# Sheet1.net
KiCad netlist of a schematic drawn in Altium Designer
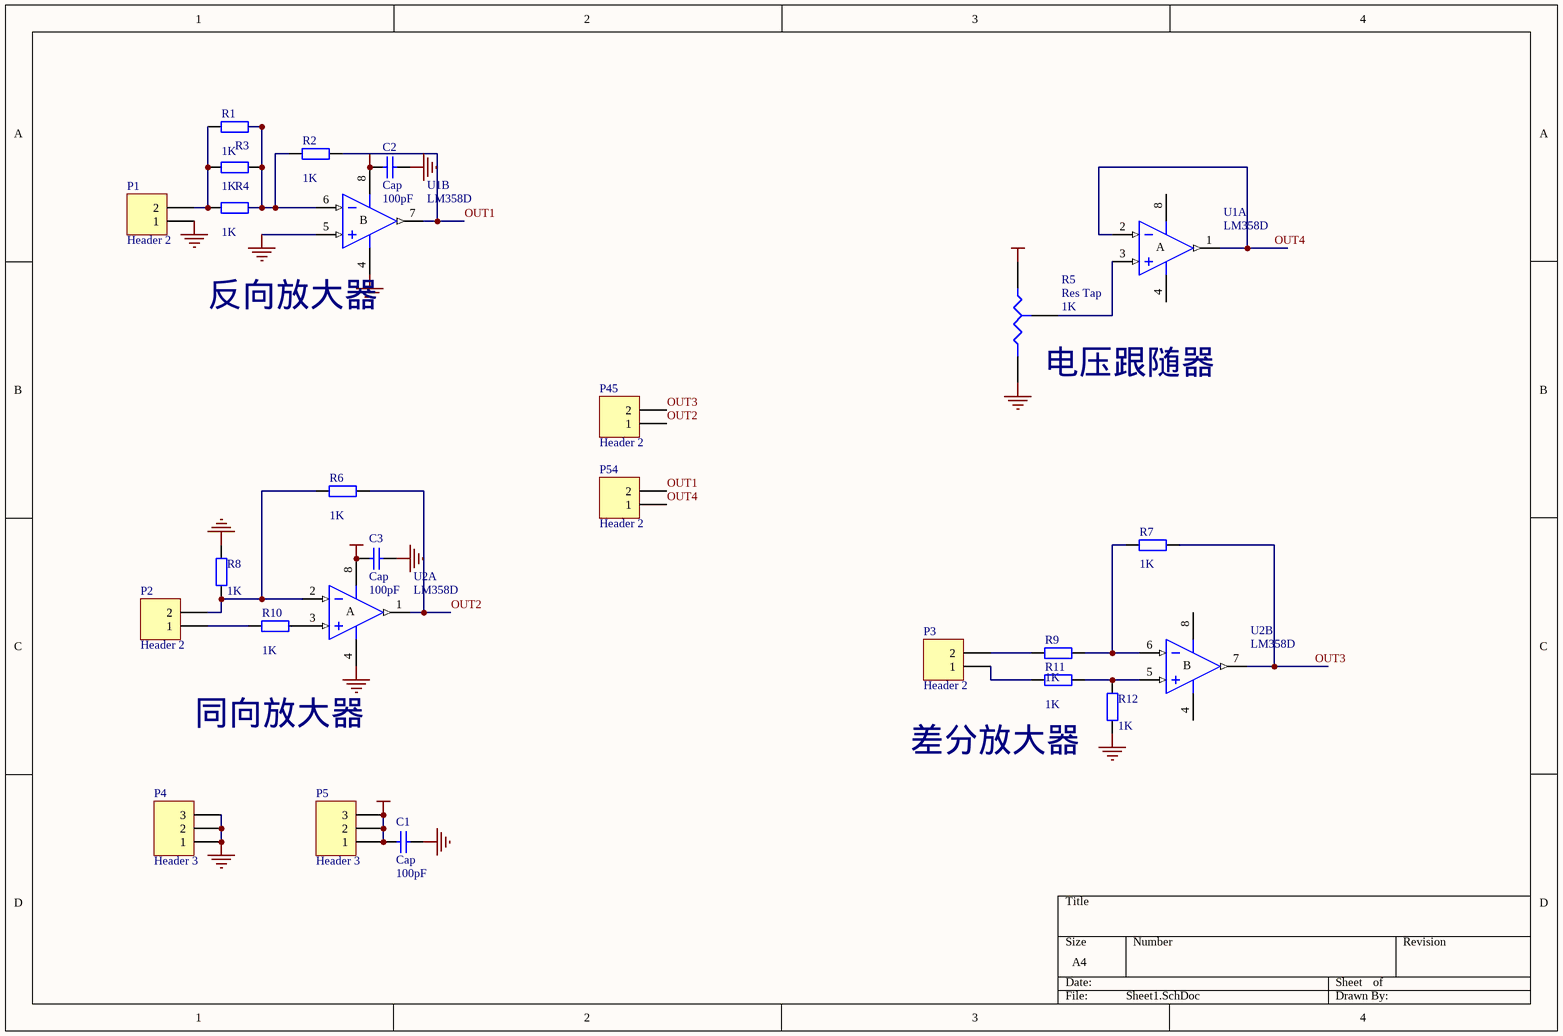
[diagram p0: Sheet1.SchDoc]

(export (version "E")
  (design (tool "Eeschema 10.0.6"))
  (components
    (comp (ref "C1")
      (value "Cap")
      (footprint "6-0805")
      (description "Capacitor")
      (fields (field (name "ALTIUM_VALUE") "100pF") (field (name "PUBLISHER") "Altium Limited"))
      (libsource (lib "Miscellaneous Devices") (part "Cap"))
    )
    (comp (ref "C2")
      (value "Cap")
      (footprint "6-0805")
      (description "Capacitor")
      (fields (field (name "ALTIUM_VALUE") "100pF") (field (name "PUBLISHER") "Altium Limited"))
      (libsource (lib "Miscellaneous Devices") (part "Cap"))
    )
    (comp (ref "C3")
      (value "Cap")
      (footprint "6-0805")
      (description "Capacitor")
      (fields (field (name "ALTIUM_VALUE") "100pF") (field (name "PUBLISHER") "Altium Limited"))
      (libsource (lib "Miscellaneous Devices") (part "Cap"))
    )
    (comp (ref "P1")
      (value "Header 2")
      (footprint "HDR1X2")
      (description "Header, 2-Pin")
      (fields (field (name "PUBLISHER") "Altium Limited"))
      (libsource (lib "Miscellaneous Connectors") (part "Header 2"))
    )
    (comp (ref "P2")
      (value "Header 2")
      (footprint "HDR1X2")
      (description "Header, 2-Pin")
      (fields (field (name "PUBLISHER") "Altium Limited"))
      (libsource (lib "Miscellaneous Connectors") (part "Header 2"))
    )
    (comp (ref "P3")
      (value "Header 2")
      (footprint "HDR1X2")
      (description "Header, 2-Pin")
      (fields (field (name "PUBLISHER") "Altium Limited"))
      (libsource (lib "Miscellaneous Connectors") (part "Header 2"))
    )
    (comp (ref "P4")
      (value "Header 3")
      (footprint "HDR1X3")
      (description "Header, 3-Pin")
      (fields (field (name "PUBLISHER") "Altium Limited"))
      (libsource (lib "Miscellaneous Connectors") (part "Header 3"))
    )
    (comp (ref "P5")
      (value "Header 3")
      (footprint "HDR1X3")
      (description "Header, 3-Pin")
      (fields (field (name "PUBLISHER") "Altium Limited"))
      (libsource (lib "Miscellaneous Connectors") (part "Header 3"))
    )
    (comp (ref "P45")
      (value "Header 2")
      (footprint "HDR1X2")
      (description "Header, 2-Pin")
      (fields (field (name "PUBLISHER") "Altium Limited"))
      (libsource (lib "Miscellaneous Connectors") (part "Header 2"))
    )
    (comp (ref "P54")
      (value "Header 2")
      (footprint "HDR1X2")
      (description "Header, 2-Pin")
      (fields (field (name "PUBLISHER") "Altium Limited"))
      (libsource (lib "Miscellaneous Connectors") (part "Header 2"))
    )
    (comp (ref "R1")
      (value "1K")
      (footprint "6-0805")
      (description "Resistor")
      (fields (field (name "Comment") "Res2") (field (name "PUBLISHER") "Altium Limited"))
      (libsource (lib "") (part "Res2_1"))
    )
    (comp (ref "R2")
      (value "1K")
      (footprint "6-0805")
      (description "Resistor")
      (fields (field (name "Comment") "Res2") (field (name "PUBLISHER") "Altium Limited"))
      (libsource (lib "") (part "Res2_2"))
    )
    (comp (ref "R3")
      (value "1K")
      (footprint "6-0805")
      (description "Resistor")
      (fields (field (name "Comment") "Res2") (field (name "PUBLISHER") "Altium Limited"))
      (libsource (lib "") (part "Res2_1"))
    )
    (comp (ref "R4")
      (value "1K")
      (footprint "6-0805")
      (description "Resistor")
      (fields (field (name "Comment") "Res2") (field (name "PUBLISHER") "Altium Limited"))
      (libsource (lib "") (part "Res2_1"))
    )
    (comp (ref "R5")
      (value "Res Tap")
      (footprint "HDR1X3")
      (description "Tapped Resistor")
      (fields (field (name "ALTIUM_VALUE") "1K") (field (name "PUBLISHER") "Altium Limited"))
      (libsource (lib "Miscellaneous Devices") (part "Res Tap"))
    )
    (comp (ref "R6")
      (value "1K")
      (footprint "6-0805")
      (description "Resistor")
      (fields (field (name "Comment") "Res2") (field (name "PUBLISHER") "Altium Limited"))
      (libsource (lib "") (part "Res2_2"))
    )
    (comp (ref "R7")
      (value "1K")
      (footprint "6-0805")
      (description "Resistor")
      (fields (field (name "Comment") "Res2") (field (name "PUBLISHER") "Altium Limited"))
      (libsource (lib "") (part "Res2_1"))
    )
    (comp (ref "R8")
      (value "1K")
      (footprint "6-0805")
      (description "Resistor")
      (fields (field (name "Comment") "Res2") (field (name "PUBLISHER") "Altium Limited"))
      (libsource (lib "") (part "Res2_3"))
    )
    (comp (ref "R9")
      (value "1K")
      (footprint "6-0805")
      (description "Resistor")
      (fields (field (name "Comment") "Res2") (field (name "PUBLISHER") "Altium Limited"))
      (libsource (lib "") (part "Res2_1"))
    )
    (comp (ref "R10")
      (value "1K")
      (footprint "6-0805")
      (description "Resistor")
      (fields (field (name "Comment") "Res2") (field (name "PUBLISHER") "Altium Limited"))
      (libsource (lib "") (part "Res2_1"))
    )
    (comp (ref "R11")
      (value "1K")
      (footprint "6-0805")
      (description "Resistor")
      (fields (field (name "Comment") "Res2") (field (name "PUBLISHER") "Altium Limited"))
      (libsource (lib "") (part "Res2_1"))
    )
    (comp (ref "R12")
      (value "1K")
      (footprint "6-0805")
      (description "Resistor")
      (fields (field (name "Comment") "Res2") (field (name "PUBLISHER") "Altium Limited"))
      (libsource (lib "Miscellaneous Devices") (part "Res2"))
    )
    (comp (ref "U1")
      (value "LM358D")
      (footprint "D008_L")
      (description "Dual Operational Amplifier")
      (fields (field (name "PUBLISHER") "Altium Limited"))
      (libsource (lib "TI Operational Amplifier") (part "LM358D"))
    )
    (comp (ref "U2")
      (value "LM358D")
      (footprint "D008_L")
      (description "Dual Operational Amplifier")
      (fields (field (name "PUBLISHER") "Altium Limited"))
      (libsource (lib "TI Operational Amplifier") (part "LM358D"))
    )
  )
  (nets
    (net (code "1") (name "+12") (class "Default")
      (node (ref "C1") (pin "1") (pinfunction "1_1") (pintype "passive"))
      (node (ref "C2") (pin "1") (pinfunction "1_1") (pintype "passive"))
      (node (ref "C3") (pin "1") (pinfunction "1_1") (pintype "passive"))
      (node (ref "P5") (pin "1") (pinfunction "1_1") (pintype "passive"))
      (node (ref "P5") (pin "2") (pinfunction "2_2") (pintype "passive"))
      (node (ref "P5") (pin "3") (pinfunction "3_3") (pintype "passive"))
      (node (ref "R5") (pin "1") (pinfunction "A_1") (pintype "passive"))
      (node (ref "U1") (pin "8") (pinfunction "V+_8") (pintype "power_in"))
      (node (ref "U2") (pin "8") (pinfunction "V+_8") (pintype "power_in"))
    )
    (net (code "2") (name "/OUT1") (class "Default")
      (node (ref "P54") (pin "2") (pinfunction "2_2") (pintype "passive"))
      (node (ref "R2") (pin "1") (pinfunction "1_1") (pintype "passive"))
      (node (ref "U1") (pin "7") (pinfunction "OUT_7") (pintype "output"))
    )
    (net (code "3") (name "/OUT2") (class "Default")
      (node (ref "P45") (pin "1") (pinfunction "1_1") (pintype "passive"))
      (node (ref "R6") (pin "1") (pinfunction "1_1") (pintype "passive"))
      (node (ref "U2") (pin "1") (pinfunction "OUT_1") (pintype "output"))
    )
    (net (code "4") (name "/OUT3") (class "Default")
      (node (ref "P45") (pin "2") (pinfunction "2_2") (pintype "passive"))
      (node (ref "R7") (pin "2") (pinfunction "2_2") (pintype "passive"))
      (node (ref "U2") (pin "7") (pinfunction "OUT_7") (pintype "output"))
    )
    (net (code "5") (name "/OUT4") (class "Default")
      (node (ref "P54") (pin "1") (pinfunction "1_1") (pintype "passive"))
      (node (ref "U1") (pin "1") (pinfunction "OUT_1") (pintype "output"))
      (node (ref "U1") (pin "2") (pinfunction "IN-_2") (pintype "input"))
    )
    (net (code "6") (name "GND") (class "Default")
      (node (ref "C1") (pin "2") (pinfunction "2_2") (pintype "passive"))
      (node (ref "C2") (pin "2") (pinfunction "2_2") (pintype "passive"))
      (node (ref "C3") (pin "2") (pinfunction "2_2") (pintype "passive"))
      (node (ref "P1") (pin "1") (pinfunction "1_1") (pintype "passive"))
      (node (ref "P4") (pin "1") (pinfunction "1_1") (pintype "passive"))
      (node (ref "P4") (pin "2") (pinfunction "2_2") (pintype "passive"))
      (node (ref "P4") (pin "3") (pinfunction "3_3") (pintype "passive"))
      (node (ref "R12") (pin "1") (pinfunction "1_1") (pintype "passive"))
      (node (ref "R5") (pin "3") (pinfunction "B_3") (pintype "passive"))
      (node (ref "R8") (pin "1") (pinfunction "1_1") (pintype "passive"))
      (node (ref "U1") (pin "4") (pinfunction "V-_4") (pintype "power_in"))
      (node (ref "U1") (pin "5") (pinfunction "IN+_5") (pintype "input"))
      (node (ref "U2") (pin "4") (pinfunction "V-_4") (pintype "power_in"))
    )
    (net (code "7") (name "Net-(P1-Pad2)") (class "Default")
      (node (ref "P1") (pin "2") (pinfunction "2_2") (pintype "passive"))
      (node (ref "R1") (pin "1") (pinfunction "1_1") (pintype "passive"))
      (node (ref "R3") (pin "1") (pinfunction "1_1") (pintype "passive"))
      (node (ref "R4") (pin "1") (pinfunction "1_1") (pintype "passive"))
    )
    (net (code "8") (name "Net-(P2-Pad1)") (class "Default")
      (node (ref "P2") (pin "1") (pinfunction "1_1") (pintype "passive"))
      (node (ref "R10") (pin "1") (pinfunction "1_1") (pintype "passive"))
    )
    (net (code "9") (name "Net-(P3-Pad1)") (class "Default")
      (node (ref "P3") (pin "1") (pinfunction "1_1") (pintype "passive"))
      (node (ref "R11") (pin "1") (pinfunction "1_1") (pintype "passive"))
    )
    (net (code "10") (name "Net-(P3-Pad2)") (class "Default")
      (node (ref "P3") (pin "2") (pinfunction "2_2") (pintype "passive"))
      (node (ref "R9") (pin "1") (pinfunction "1_1") (pintype "passive"))
    )
    (net (code "11") (name "Net-(R5-TAP)") (class "Default")
      (node (ref "R5") (pin "2") (pinfunction "TAP_2") (pintype "passive"))
      (node (ref "U1") (pin "3") (pinfunction "IN+_3") (pintype "input"))
    )
    (net (code "12") (name "Net-(U1B-IN-)") (class "Default")
      (node (ref "R1") (pin "2") (pinfunction "2_2") (pintype "passive"))
      (node (ref "R2") (pin "2") (pinfunction "2_2") (pintype "passive"))
      (node (ref "R3") (pin "2") (pinfunction "2_2") (pintype "passive"))
      (node (ref "R4") (pin "2") (pinfunction "2_2") (pintype "passive"))
      (node (ref "U1") (pin "6") (pinfunction "IN-_6") (pintype "input"))
    )
    (net (code "13") (name "Net-(U2A-IN+)") (class "Default")
      (node (ref "R10") (pin "2") (pinfunction "2_2") (pintype "passive"))
      (node (ref "U2") (pin "3") (pinfunction "IN+_3") (pintype "input"))
    )
    (net (code "14") (name "Net-(U2A-IN-)") (class "Default")
      (node (ref "P2") (pin "2") (pinfunction "2_2") (pintype "passive"))
      (node (ref "R6") (pin "2") (pinfunction "2_2") (pintype "passive"))
      (node (ref "R8") (pin "2") (pinfunction "2_2") (pintype "passive"))
      (node (ref "U2") (pin "2") (pinfunction "IN-_2") (pintype "input"))
    )
    (net (code "15") (name "Net-(U2B-IN+)") (class "Default")
      (node (ref "R11") (pin "2") (pinfunction "2_2") (pintype "passive"))
      (node (ref "R12") (pin "2") (pinfunction "2_2") (pintype "passive"))
      (node (ref "U2") (pin "5") (pinfunction "IN+_5") (pintype "input"))
    )
    (net (code "16") (name "Net-(U2B-IN-)") (class "Default")
      (node (ref "R7") (pin "1") (pinfunction "1_1") (pintype "passive"))
      (node (ref "R9") (pin "2") (pinfunction "2_2") (pintype "passive"))
      (node (ref "U2") (pin "6") (pinfunction "IN-_6") (pintype "input"))
    )
    (net (code "17") (name "unconnected-(U1A-V+-Pad8)") (class "Default")
      (node (ref "U1") (pin "8") (pinfunction "V+_8") (pintype "power_in"))
    )
    (net (code "18") (name "unconnected-(U1A-V--Pad4)") (class "Default")
      (node (ref "U1") (pin "4") (pinfunction "V-_4") (pintype "power_in"))
    )
    (net (code "19") (name "unconnected-(U2B-V+-Pad8)") (class "Default")
      (node (ref "U2") (pin "8") (pinfunction "V+_8") (pintype "power_in"))
    )
    (net (code "20") (name "unconnected-(U2B-V--Pad4)") (class "Default")
      (node (ref "U2") (pin "4") (pinfunction "V-_4") (pintype "power_in"))
    )
  )
)
